# co-processor.net
KiCad netlist of a schematic drawn in EAGLE
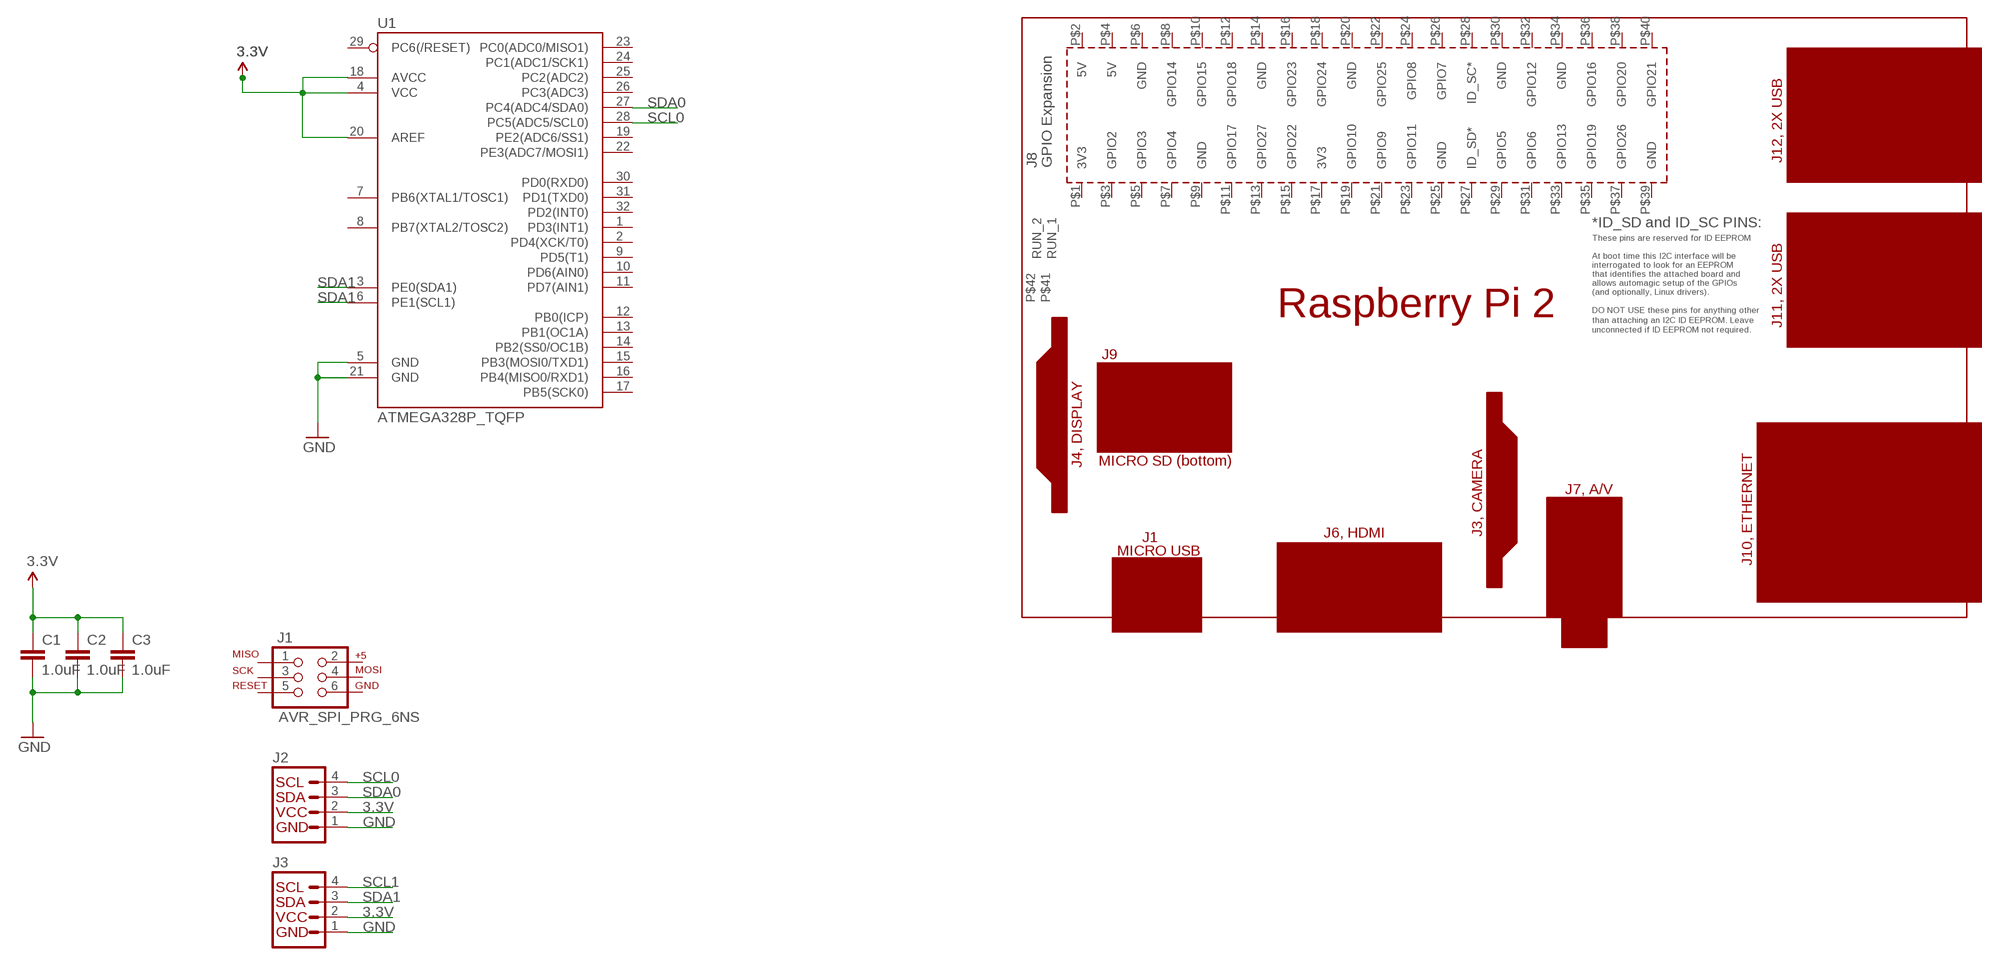
[diagram p0: schematic, sheet 1]

(export (version "E")
  (design (tool "Eeschema 10.0.6"))
  (components
    (comp (ref "C1")
      (value "1.0uF")
      (footprint "eagle-import:0603-CAP")
      (libsource (lib "eagle-import") (part "1.0UF-16V-10%(0603)"))
    )
    (comp (ref "C2")
      (value "1.0uF")
      (footprint "eagle-import:0603-CAP")
      (libsource (lib "eagle-import") (part "1.0UF-16V-10%(0603)"))
    )
    (comp (ref "C3")
      (value "1.0uF")
      (footprint "eagle-import:0603-CAP")
      (libsource (lib "eagle-import") (part "1.0UF-16V-10%(0603)"))
    )
    (comp (ref "J1")
      (value "AVR_SPI_PRG_6NS")
      (footprint "eagle-import:2X3-NS")
      (libsource (lib "eagle-import") (part "AVR_SPI_PRG_6NS"))
    )
    (comp (ref "J2")
      (value "I2C_STANDARD")
      (footprint "eagle-import:1X04")
      (libsource (lib "eagle-import") (part "I2C_STANDARD"))
    )
    (comp (ref "J3")
      (value "I2C_STANDARD")
      (footprint "eagle-import:1X04")
      (libsource (lib "eagle-import") (part "I2C_STANDARD"))
    )
    (comp (ref "PCB1")
      (value "RPI2")
      (footprint "eagle-import:RPI2")
      (libsource (lib "eagle-import") (part "RPI2"))
    )
    (comp (ref "U1")
      (value "ATMEGA328P_TQFP")
      (footprint "eagle-import:TQFP32-08")
      (libsource (lib "eagle-import") (part "ATMEGA328PB_TQFP"))
    )
  )
  (nets
    (net (code "1") (name "/SCL0") (class "Default")
      (node (ref "J2") (pin "4") (pinfunction "4_4") (pintype "passive"))
      (node (ref "U1") (pin "28") (pinfunction "PC5(ADC5/SCL0)_28") (pintype "bidirectional"))
    )
    (net (code "2") (name "/SCL1") (class "Default")
      (node (ref "J3") (pin "4") (pinfunction "4_4") (pintype "passive"))
    )
    (net (code "3") (name "/SDA0") (class "Default")
      (node (ref "J2") (pin "3") (pinfunction "3_3") (pintype "passive"))
      (node (ref "U1") (pin "27") (pinfunction "PC4(ADC4/SDA0)_27") (pintype "bidirectional"))
    )
    (net (code "4") (name "/SDA1") (class "Default")
      (node (ref "J3") (pin "3") (pinfunction "3_3") (pintype "passive"))
      (node (ref "U1") (pin "3") (pinfunction "PE0(SDA1)_3") (pintype "bidirectional"))
      (node (ref "U1") (pin "6") (pinfunction "PE1(SCL1)_6") (pintype "bidirectional"))
    )
    (net (code "5") (name "3.3V") (class "Default")
      (node (ref "C1") (pin "1") (pinfunction "1_1") (pintype "passive"))
      (node (ref "C2") (pin "1") (pinfunction "1_1") (pintype "passive"))
      (node (ref "C3") (pin "1") (pinfunction "1_1") (pintype "passive"))
      (node (ref "J2") (pin "2") (pinfunction "2_2") (pintype "passive"))
      (node (ref "J3") (pin "2") (pinfunction "2_2") (pintype "passive"))
      (node (ref "U1") (pin "18") (pinfunction "AVCC_18") (pintype "bidirectional"))
      (node (ref "U1") (pin "20") (pinfunction "AREF_20") (pintype "bidirectional"))
      (node (ref "U1") (pin "4") (pinfunction "VCC_4") (pintype "bidirectional"))
    )
    (net (code "6") (name "GND") (class "Default")
      (node (ref "C1") (pin "2") (pinfunction "2_2") (pintype "passive"))
      (node (ref "C2") (pin "2") (pinfunction "2_2") (pintype "passive"))
      (node (ref "C3") (pin "2") (pinfunction "2_2") (pintype "passive"))
      (node (ref "J2") (pin "1") (pinfunction "1_1") (pintype "passive"))
      (node (ref "J3") (pin "1") (pinfunction "1_1") (pintype "passive"))
      (node (ref "U1") (pin "21") (pinfunction "GND_21") (pintype "bidirectional"))
      (node (ref "U1") (pin "5") (pinfunction "GND_5") (pintype "bidirectional"))
    )
    (net (code "7") (name "unconnected-(J1-Pad1)") (class "Default")
      (node (ref "J1") (pin "1") (pinfunction "1_1") (pintype "passive"))
    )
    (net (code "8") (name "unconnected-(J1-Pad2)") (class "Default")
      (node (ref "J1") (pin "2") (pinfunction "2_2") (pintype "passive"))
    )
    (net (code "9") (name "unconnected-(J1-Pad3)") (class "Default")
      (node (ref "J1") (pin "3") (pinfunction "3_3") (pintype "passive"))
    )
    (net (code "10") (name "unconnected-(J1-Pad4)") (class "Default")
      (node (ref "J1") (pin "4") (pinfunction "4_4") (pintype "passive"))
    )
    (net (code "11") (name "unconnected-(J1-Pad5)") (class "Default")
      (node (ref "J1") (pin "5") (pinfunction "5_5") (pintype "passive"))
    )
    (net (code "12") (name "unconnected-(J1-Pad6)") (class "Default")
      (node (ref "J1") (pin "6") (pinfunction "6_6") (pintype "passive"))
    )
    (net (code "13") (name "unconnected-(PCB1-3V3-PadP$1)") (class "Default")
      (node (ref "PCB1") (pin "P$1") (pinfunction "3V3_P$1") (pintype "bidirectional"))
    )
    (net (code "14") (name "unconnected-(PCB1-3V3-PadP$17)") (class "Default")
      (node (ref "PCB1") (pin "P$17") (pinfunction "3V3_P$17") (pintype "bidirectional"))
    )
    (net (code "15") (name "unconnected-(PCB1-5V-PadP$2)") (class "Default")
      (node (ref "PCB1") (pin "P$2") (pinfunction "5V_P$2") (pintype "bidirectional"))
    )
    (net (code "16") (name "unconnected-(PCB1-5V-PadP$4)") (class "Default")
      (node (ref "PCB1") (pin "P$4") (pinfunction "5V_P$4") (pintype "bidirectional"))
    )
    (net (code "17") (name "unconnected-(PCB1-GND-PadP$6)") (class "Default")
      (node (ref "PCB1") (pin "P$6") (pinfunction "GND_P$6") (pintype "bidirectional"))
    )
    (net (code "18") (name "unconnected-(PCB1-GND-PadP$9)") (class "Default")
      (node (ref "PCB1") (pin "P$9") (pinfunction "GND_P$9") (pintype "bidirectional"))
    )
    (net (code "19") (name "unconnected-(PCB1-GND-PadP$14)") (class "Default")
      (node (ref "PCB1") (pin "P$14") (pinfunction "GND_P$14") (pintype "bidirectional"))
    )
    (net (code "20") (name "unconnected-(PCB1-GND-PadP$20)") (class "Default")
      (node (ref "PCB1") (pin "P$20") (pinfunction "GND_P$20") (pintype "bidirectional"))
    )
    (net (code "21") (name "unconnected-(PCB1-GND-PadP$25)") (class "Default")
      (node (ref "PCB1") (pin "P$25") (pinfunction "GND_P$25") (pintype "bidirectional"))
    )
    (net (code "22") (name "unconnected-(PCB1-GND-PadP$30)") (class "Default")
      (node (ref "PCB1") (pin "P$30") (pinfunction "GND_P$30") (pintype "bidirectional"))
    )
    (net (code "23") (name "unconnected-(PCB1-GND-PadP$34)") (class "Default")
      (node (ref "PCB1") (pin "P$34") (pinfunction "GND_P$34") (pintype "bidirectional"))
    )
    (net (code "24") (name "unconnected-(PCB1-GND-PadP$39)") (class "Default")
      (node (ref "PCB1") (pin "P$39") (pinfunction "GND_P$39") (pintype "bidirectional"))
    )
    (net (code "25") (name "unconnected-(PCB1-GPIO2-PadP$3)") (class "Default")
      (node (ref "PCB1") (pin "P$3") (pinfunction "GPIO2_P$3") (pintype "bidirectional"))
    )
    (net (code "26") (name "unconnected-(PCB1-GPIO3-PadP$5)") (class "Default")
      (node (ref "PCB1") (pin "P$5") (pinfunction "GPIO3_P$5") (pintype "bidirectional"))
    )
    (net (code "27") (name "unconnected-(PCB1-GPIO4-PadP$7)") (class "Default")
      (node (ref "PCB1") (pin "P$7") (pinfunction "GPIO4_P$7") (pintype "bidirectional"))
    )
    (net (code "28") (name "unconnected-(PCB1-GPIO5-PadP$29)") (class "Default")
      (node (ref "PCB1") (pin "P$29") (pinfunction "GPIO5_P$29") (pintype "bidirectional"))
    )
    (net (code "29") (name "unconnected-(PCB1-GPIO6-PadP$31)") (class "Default")
      (node (ref "PCB1") (pin "P$31") (pinfunction "GPIO6_P$31") (pintype "bidirectional"))
    )
    (net (code "30") (name "unconnected-(PCB1-GPIO7-PadP$26)") (class "Default")
      (node (ref "PCB1") (pin "P$26") (pinfunction "GPIO7_P$26") (pintype "bidirectional"))
    )
    (net (code "31") (name "unconnected-(PCB1-GPIO8-PadP$24)") (class "Default")
      (node (ref "PCB1") (pin "P$24") (pinfunction "GPIO8_P$24") (pintype "bidirectional"))
    )
    (net (code "32") (name "unconnected-(PCB1-GPIO9-PadP$21)") (class "Default")
      (node (ref "PCB1") (pin "P$21") (pinfunction "GPIO9_P$21") (pintype "bidirectional"))
    )
    (net (code "33") (name "unconnected-(PCB1-GPIO10-PadP$19)") (class "Default")
      (node (ref "PCB1") (pin "P$19") (pinfunction "GPIO10_P$19") (pintype "bidirectional"))
    )
    (net (code "34") (name "unconnected-(PCB1-GPIO11-PadP$23)") (class "Default")
      (node (ref "PCB1") (pin "P$23") (pinfunction "GPIO11_P$23") (pintype "bidirectional"))
    )
    (net (code "35") (name "unconnected-(PCB1-GPIO12-PadP$32)") (class "Default")
      (node (ref "PCB1") (pin "P$32") (pinfunction "GPIO12_P$32") (pintype "bidirectional"))
    )
    (net (code "36") (name "unconnected-(PCB1-GPIO13-PadP$33)") (class "Default")
      (node (ref "PCB1") (pin "P$33") (pinfunction "GPIO13_P$33") (pintype "bidirectional"))
    )
    (net (code "37") (name "unconnected-(PCB1-GPIO14-PadP$8)") (class "Default")
      (node (ref "PCB1") (pin "P$8") (pinfunction "GPIO14_P$8") (pintype "bidirectional"))
    )
    (net (code "38") (name "unconnected-(PCB1-GPIO15-PadP$10)") (class "Default")
      (node (ref "PCB1") (pin "P$10") (pinfunction "GPIO15_P$10") (pintype "bidirectional"))
    )
    (net (code "39") (name "unconnected-(PCB1-GPIO16-PadP$36)") (class "Default")
      (node (ref "PCB1") (pin "P$36") (pinfunction "GPIO16_P$36") (pintype "bidirectional"))
    )
    (net (code "40") (name "unconnected-(PCB1-GPIO17-PadP$11)") (class "Default")
      (node (ref "PCB1") (pin "P$11") (pinfunction "GPIO17_P$11") (pintype "bidirectional"))
    )
    (net (code "41") (name "unconnected-(PCB1-GPIO18-PadP$12)") (class "Default")
      (node (ref "PCB1") (pin "P$12") (pinfunction "GPIO18_P$12") (pintype "bidirectional"))
    )
    (net (code "42") (name "unconnected-(PCB1-GPIO19-PadP$35)") (class "Default")
      (node (ref "PCB1") (pin "P$35") (pinfunction "GPIO19_P$35") (pintype "bidirectional"))
    )
    (net (code "43") (name "unconnected-(PCB1-GPIO20-PadP$38)") (class "Default")
      (node (ref "PCB1") (pin "P$38") (pinfunction "GPIO20_P$38") (pintype "bidirectional"))
    )
    (net (code "44") (name "unconnected-(PCB1-GPIO21-PadP$40)") (class "Default")
      (node (ref "PCB1") (pin "P$40") (pinfunction "GPIO21_P$40") (pintype "bidirectional"))
    )
    (net (code "45") (name "unconnected-(PCB1-GPIO22-PadP$15)") (class "Default")
      (node (ref "PCB1") (pin "P$15") (pinfunction "GPIO22_P$15") (pintype "bidirectional"))
    )
    (net (code "46") (name "unconnected-(PCB1-GPIO23-PadP$16)") (class "Default")
      (node (ref "PCB1") (pin "P$16") (pinfunction "GPIO23_P$16") (pintype "bidirectional"))
    )
    (net (code "47") (name "unconnected-(PCB1-GPIO24-PadP$18)") (class "Default")
      (node (ref "PCB1") (pin "P$18") (pinfunction "GPIO24_P$18") (pintype "bidirectional"))
    )
    (net (code "48") (name "unconnected-(PCB1-GPIO25-PadP$22)") (class "Default")
      (node (ref "PCB1") (pin "P$22") (pinfunction "GPIO25_P$22") (pintype "bidirectional"))
    )
    (net (code "49") (name "unconnected-(PCB1-GPIO26-PadP$37)") (class "Default")
      (node (ref "PCB1") (pin "P$37") (pinfunction "GPIO26_P$37") (pintype "bidirectional"))
    )
    (net (code "50") (name "unconnected-(PCB1-GPIO27-PadP$13)") (class "Default")
      (node (ref "PCB1") (pin "P$13") (pinfunction "GPIO27_P$13") (pintype "bidirectional"))
    )
    (net (code "51") (name "unconnected-(PCB1-ID_SC*-PadP$28)") (class "Default")
      (node (ref "PCB1") (pin "P$28") (pinfunction "ID_SC*_P$28") (pintype "bidirectional"))
    )
    (net (code "52") (name "unconnected-(PCB1-ID_SD*-PadP$27)") (class "Default")
      (node (ref "PCB1") (pin "P$27") (pinfunction "ID_SD*_P$27") (pintype "bidirectional"))
    )
    (net (code "53") (name "unconnected-(PCB1-RUN_1-PadP$41)") (class "Default")
      (node (ref "PCB1") (pin "P$41") (pinfunction "RUN_1_P$41") (pintype "bidirectional"))
    )
    (net (code "54") (name "unconnected-(PCB1-RUN_2-PadP$42)") (class "Default")
      (node (ref "PCB1") (pin "P$42") (pinfunction "RUN_2_P$42") (pintype "bidirectional"))
    )
    (net (code "55") (name "unconnected-(U1-PB0(ICP)-Pad12)") (class "Default")
      (node (ref "U1") (pin "12") (pinfunction "PB0(ICP)_12") (pintype "bidirectional"))
    )
    (net (code "56") (name "unconnected-(U1-PB1(OC1A)-Pad13)") (class "Default")
      (node (ref "U1") (pin "13") (pinfunction "PB1(OC1A)_13") (pintype "bidirectional"))
    )
    (net (code "57") (name "unconnected-(U1-PB2(SS0{slash}OC1B)-Pad14)") (class "Default")
      (node (ref "U1") (pin "14") (pinfunction "PB2(SS0/OC1B)_14") (pintype "bidirectional"))
    )
    (net (code "58") (name "unconnected-(U1-PB3(MOSI0{slash}TXD1)-Pad15)") (class "Default")
      (node (ref "U1") (pin "15") (pinfunction "PB3(MOSI0/TXD1)_15") (pintype "bidirectional"))
    )
    (net (code "59") (name "unconnected-(U1-PB4(MISO0{slash}RXD1)-Pad16)") (class "Default")
      (node (ref "U1") (pin "16") (pinfunction "PB4(MISO0/RXD1)_16") (pintype "bidirectional"))
    )
    (net (code "60") (name "unconnected-(U1-PB5(SCK0)-Pad17)") (class "Default")
      (node (ref "U1") (pin "17") (pinfunction "PB5(SCK0)_17") (pintype "bidirectional"))
    )
    (net (code "61") (name "unconnected-(U1-PB6(XTAL1{slash}TOSC1)-Pad7)") (class "Default")
      (node (ref "U1") (pin "7") (pinfunction "PB6(XTAL1/TOSC1)_7") (pintype "bidirectional"))
    )
    (net (code "62") (name "unconnected-(U1-PB7(XTAL2{slash}TOSC2)-Pad8)") (class "Default")
      (node (ref "U1") (pin "8") (pinfunction "PB7(XTAL2/TOSC2)_8") (pintype "bidirectional"))
    )
    (net (code "63") (name "unconnected-(U1-PC0(ADC0{slash}MISO1)-Pad23)") (class "Default")
      (node (ref "U1") (pin "23") (pinfunction "PC0(ADC0/MISO1)_23") (pintype "bidirectional"))
    )
    (net (code "64") (name "unconnected-(U1-PC1(ADC1{slash}SCK1)-Pad24)") (class "Default")
      (node (ref "U1") (pin "24") (pinfunction "PC1(ADC1/SCK1)_24") (pintype "bidirectional"))
    )
    (net (code "65") (name "unconnected-(U1-PC2(ADC2)-Pad25)") (class "Default")
      (node (ref "U1") (pin "25") (pinfunction "PC2(ADC2)_25") (pintype "bidirectional"))
    )
    (net (code "66") (name "unconnected-(U1-PC3(ADC3)-Pad26)") (class "Default")
      (node (ref "U1") (pin "26") (pinfunction "PC3(ADC3)_26") (pintype "bidirectional"))
    )
    (net (code "67") (name "unconnected-(U1-PC6({slash}RESET)-Pad29)") (class "Default")
      (node (ref "U1") (pin "29") (pinfunction "PC6(/RESET)_29") (pintype "bidirectional"))
    )
    (net (code "68") (name "unconnected-(U1-PD0(RXD0)-Pad30)") (class "Default")
      (node (ref "U1") (pin "30") (pinfunction "PD0(RXD0)_30") (pintype "bidirectional"))
    )
    (net (code "69") (name "unconnected-(U1-PD1(TXD0)-Pad31)") (class "Default")
      (node (ref "U1") (pin "31") (pinfunction "PD1(TXD0)_31") (pintype "bidirectional"))
    )
    (net (code "70") (name "unconnected-(U1-PD2(INT0)-Pad32)") (class "Default")
      (node (ref "U1") (pin "32") (pinfunction "PD2(INT0)_32") (pintype "bidirectional"))
    )
    (net (code "71") (name "unconnected-(U1-PD3(INT1)-Pad1)") (class "Default")
      (node (ref "U1") (pin "1") (pinfunction "PD3(INT1)_1") (pintype "bidirectional"))
    )
    (net (code "72") (name "unconnected-(U1-PD4(XCK{slash}T0)-Pad2)") (class "Default")
      (node (ref "U1") (pin "2") (pinfunction "PD4(XCK/T0)_2") (pintype "bidirectional"))
    )
    (net (code "73") (name "unconnected-(U1-PD5(T1)-Pad9)") (class "Default")
      (node (ref "U1") (pin "9") (pinfunction "PD5(T1)_9") (pintype "bidirectional"))
    )
    (net (code "74") (name "unconnected-(U1-PD6(AIN0)-Pad10)") (class "Default")
      (node (ref "U1") (pin "10") (pinfunction "PD6(AIN0)_10") (pintype "bidirectional"))
    )
    (net (code "75") (name "unconnected-(U1-PD7(AIN1)-Pad11)") (class "Default")
      (node (ref "U1") (pin "11") (pinfunction "PD7(AIN1)_11") (pintype "bidirectional"))
    )
    (net (code "76") (name "unconnected-(U1-PE2(ADC6{slash}SS1)-Pad19)") (class "Default")
      (node (ref "U1") (pin "19") (pinfunction "PE2(ADC6/SS1)_19") (pintype "bidirectional"))
    )
    (net (code "77") (name "unconnected-(U1-PE3(ADC7{slash}MOSI1)-Pad22)") (class "Default")
      (node (ref "U1") (pin "22") (pinfunction "PE3(ADC7/MOSI1)_22") (pintype "bidirectional"))
    )
  )
)
